# WL-ATT.net
KiCad netlist of a schematic drawn in Altium Designer
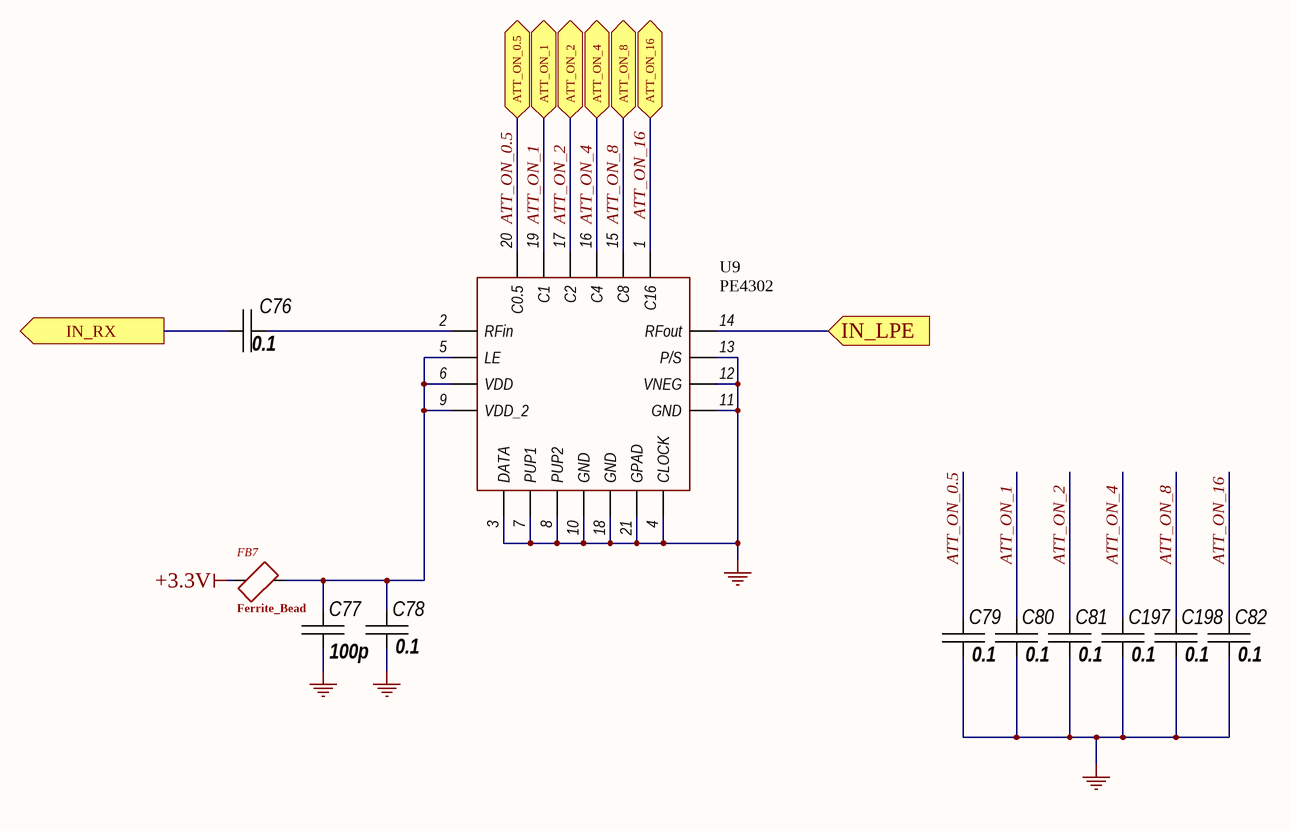
[diagram p0: WL-ATT.SchDoc]

(export (version "E")
  (design (tool "Eeschema 10.0.6"))
  (components
    (comp (ref "C76")
      (value "0.1")
      (footprint "standard:CH0805C")
      (libsource (lib "Discrete") (part "Capacitor"))
    )
    (comp (ref "C77")
      (value "100p")
      (footprint "standard:CH0805C")
      (libsource (lib "Discrete") (part "Capacitor"))
    )
    (comp (ref "C78")
      (value "0.1")
      (footprint "standard:CH0805C")
      (libsource (lib "Discrete") (part "Capacitor"))
    )
    (comp (ref "C79")
      (value "0.1")
      (footprint "standard:CH0805C")
      (libsource (lib "Discrete") (part "Capacitor"))
    )
    (comp (ref "C80")
      (value "0.1")
      (footprint "standard:CH0805C")
      (libsource (lib "Discrete") (part "Capacitor"))
    )
    (comp (ref "C81")
      (value "0.1")
      (footprint "standard:CH0805C")
      (libsource (lib "Discrete") (part "Capacitor"))
    )
    (comp (ref "C82")
      (value "0.1")
      (footprint "standard:CH0805C")
      (libsource (lib "Discrete") (part "Capacitor"))
    )
    (comp (ref "C197")
      (value "0.1")
      (footprint "standard:CH0805C")
      (libsource (lib "Discrete") (part "Capacitor"))
    )
    (comp (ref "C198")
      (value "0.1")
      (footprint "standard:CH0805C")
      (libsource (lib "Discrete") (part "Capacitor"))
    )
    (comp (ref "FB7") (value "Ferrite_Bead") (footprint "CH0805L") (libsource (lib "Discrete") (part "FB")))
    (comp (ref "U9") (value "PE4302") (footprint "20-QFN (4x4)") (libsource (lib "Digital") (part "PE4302")))
  )
  (nets
    (net (code "1") (name "+3.3V") (class "Default")
      (node (ref "FB7") (pin "2") (pinfunction "2_2") (pintype "passive"))
    )
    (net (code "2") (name "/ATT_ON_0.5") (class "Default")
      (node (ref "C79") (pin "2") (pinfunction "2_2") (pintype "power_in"))
      (node (ref "U9") (pin "20") (pinfunction "C0.5_20") (pintype "passive"))
    )
    (net (code "3") (name "/ATT_ON_1") (class "Default")
      (node (ref "C80") (pin "2") (pinfunction "2_2") (pintype "power_in"))
      (node (ref "U9") (pin "19") (pinfunction "C1_19") (pintype "passive"))
    )
    (net (code "4") (name "/ATT_ON_2") (class "Default")
      (node (ref "C81") (pin "2") (pinfunction "2_2") (pintype "power_in"))
      (node (ref "U9") (pin "17") (pinfunction "C2_17") (pintype "passive"))
    )
    (net (code "5") (name "/ATT_ON_4") (class "Default")
      (node (ref "C197") (pin "2") (pinfunction "2_2") (pintype "power_in"))
      (node (ref "U9") (pin "16") (pinfunction "C4_16") (pintype "passive"))
    )
    (net (code "6") (name "/ATT_ON_8") (class "Default")
      (node (ref "C198") (pin "2") (pinfunction "2_2") (pintype "power_in"))
      (node (ref "U9") (pin "15") (pinfunction "C8_15") (pintype "passive"))
    )
    (net (code "7") (name "/ATT_ON_16") (class "Default")
      (node (ref "C82") (pin "2") (pinfunction "2_2") (pintype "power_in"))
      (node (ref "U9") (pin "1") (pinfunction "C16_1") (pintype "passive"))
    )
    (net (code "8") (name "/IN_LPE") (class "Default")
      (node (ref "U9") (pin "14") (pinfunction "RFout_14") (pintype "passive"))
    )
    (net (code "9") (name "/IN_RX") (class "Default")
      (node (ref "C76") (pin "1") (pinfunction "1_1") (pintype "power_in"))
    )
    (net (code "10") (name "GND") (class "Default")
      (node (ref "C197") (pin "1") (pinfunction "1_1") (pintype "power_in"))
      (node (ref "C198") (pin "1") (pinfunction "1_1") (pintype "power_in"))
      (node (ref "C77") (pin "1") (pinfunction "1_1") (pintype "power_in"))
      (node (ref "C78") (pin "1") (pinfunction "1_1") (pintype "power_in"))
      (node (ref "C79") (pin "1") (pinfunction "1_1") (pintype "power_in"))
      (node (ref "C80") (pin "1") (pinfunction "1_1") (pintype "power_in"))
      (node (ref "C81") (pin "1") (pinfunction "1_1") (pintype "power_in"))
      (node (ref "C82") (pin "1") (pinfunction "1_1") (pintype "power_in"))
      (node (ref "U9") (pin "10") (pinfunction "GND_10") (pintype "passive"))
      (node (ref "U9") (pin "11") (pinfunction "GND_11") (pintype "passive"))
      (node (ref "U9") (pin "12") (pinfunction "VNEG_12") (pintype "passive"))
      (node (ref "U9") (pin "13") (pinfunction "P/S_13") (pintype "passive"))
      (node (ref "U9") (pin "18") (pinfunction "GND_18") (pintype "passive"))
      (node (ref "U9") (pin "21") (pinfunction "GPAD_21") (pintype "passive"))
      (node (ref "U9") (pin "3") (pinfunction "DATA_3") (pintype "passive"))
      (node (ref "U9") (pin "4") (pinfunction "CLOCK_4") (pintype "passive"))
      (node (ref "U9") (pin "7") (pinfunction "PUP1_7") (pintype "passive"))
      (node (ref "U9") (pin "8") (pinfunction "PUP2_8") (pintype "passive"))
    )
    (net (code "11") (name "Net-(U9-LE)") (class "Default")
      (node (ref "C77") (pin "2") (pinfunction "2_2") (pintype "power_in"))
      (node (ref "C78") (pin "2") (pinfunction "2_2") (pintype "power_in"))
      (node (ref "FB7") (pin "1") (pinfunction "1_1") (pintype "passive"))
      (node (ref "U9") (pin "5") (pinfunction "LE_5") (pintype "passive"))
      (node (ref "U9") (pin "6") (pinfunction "VDD_6") (pintype "passive"))
      (node (ref "U9") (pin "9") (pinfunction "VDD_2_9") (pintype "passive"))
    )
    (net (code "12") (name "Net-(U9-RFin)") (class "Default")
      (node (ref "C76") (pin "2") (pinfunction "2_2") (pintype "power_in"))
      (node (ref "U9") (pin "2") (pinfunction "RFin_2") (pintype "passive"))
    )
  )
)
